# full_board.net
KiCad netlist of a schematic drawn in EAGLE
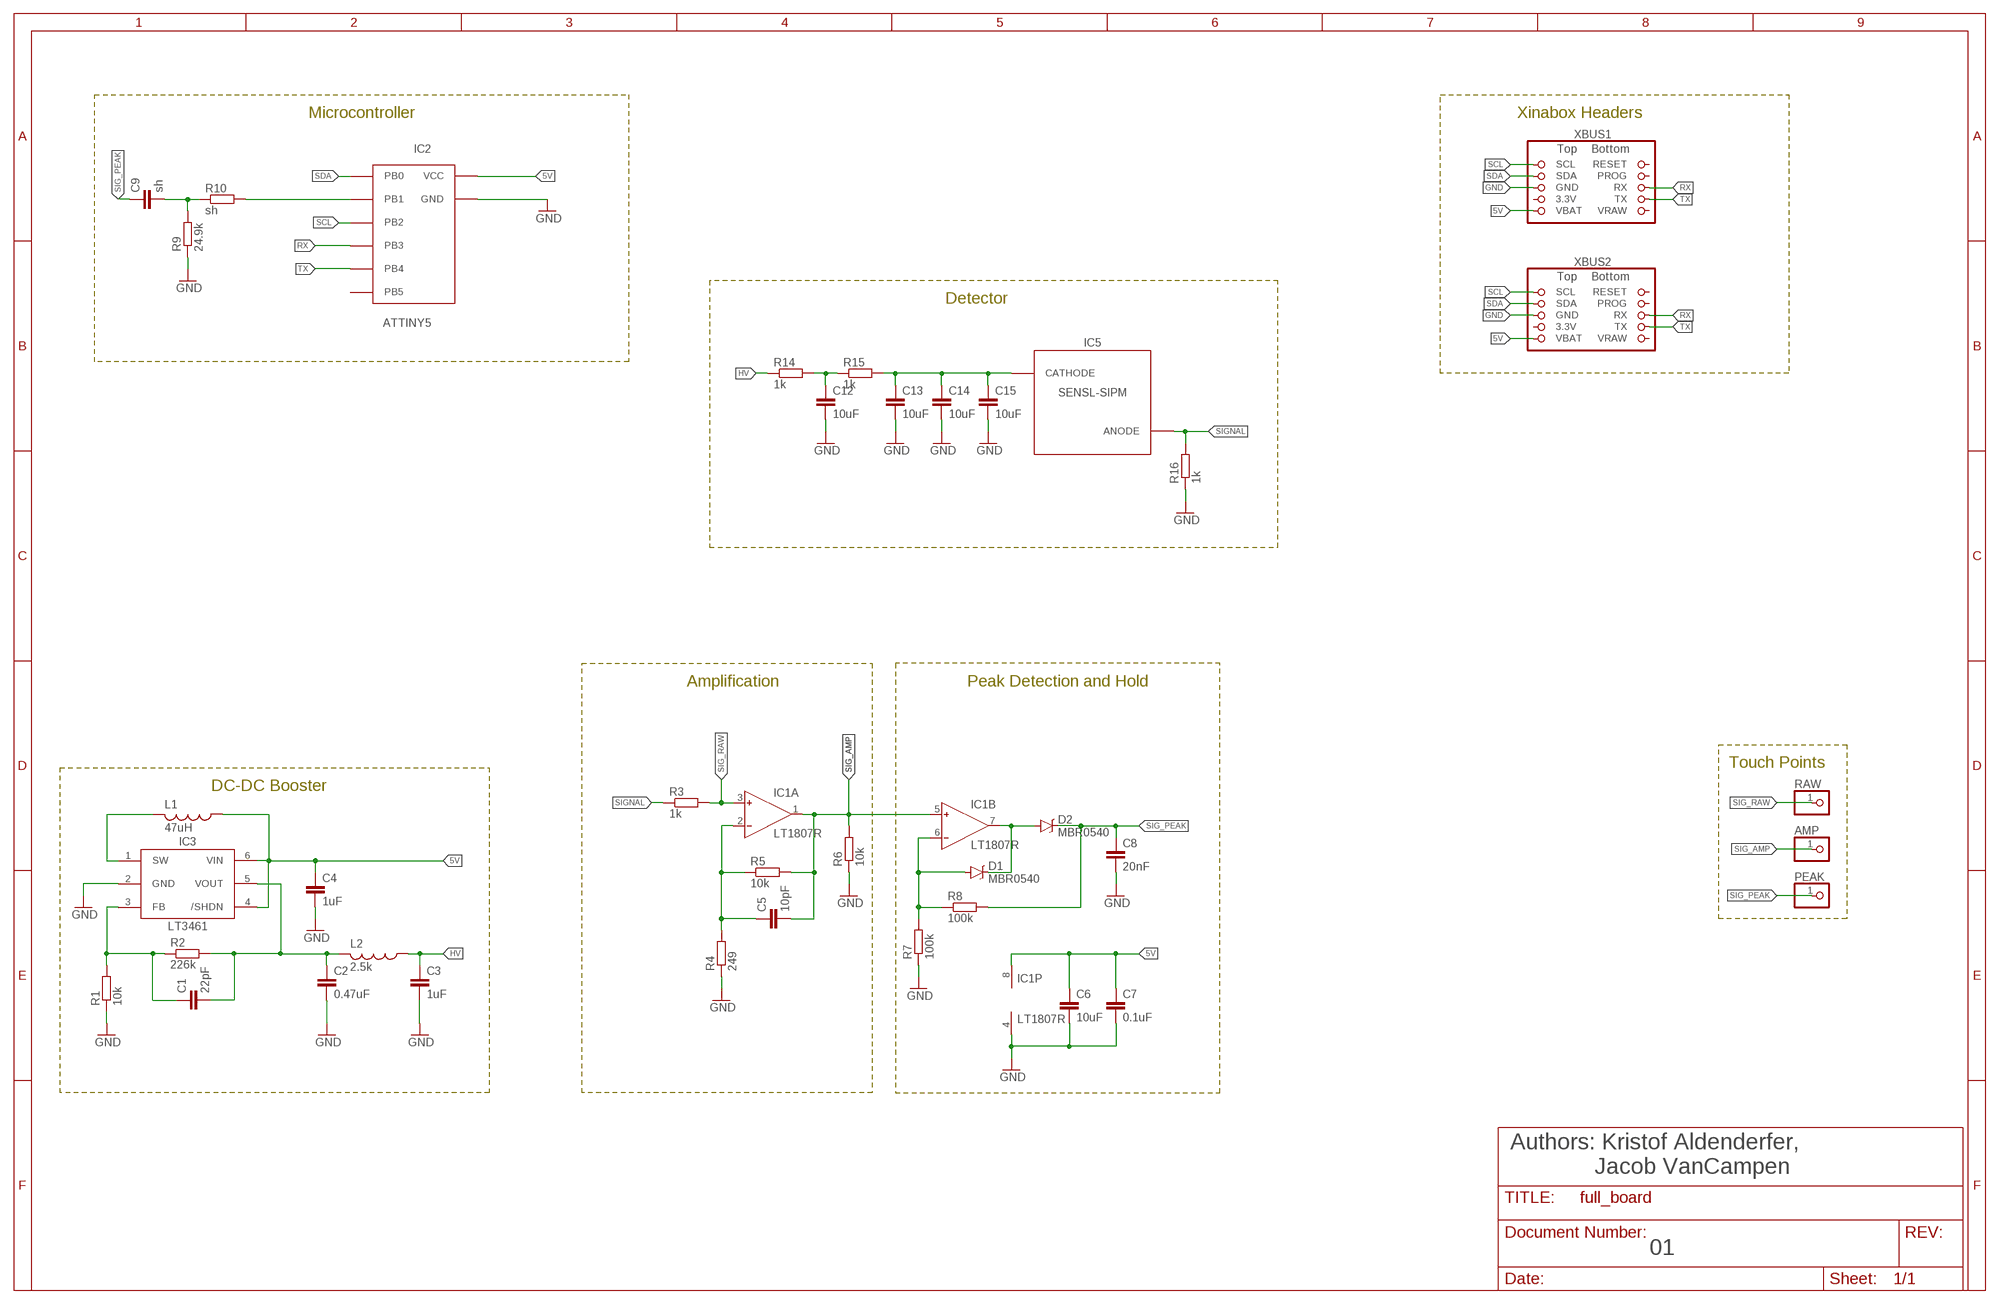
[diagram p0: schematic, sheet 1]

(export (version "E")
  (design (tool "Eeschema 10.0.6"))
  (components
    (comp (ref "AMP")
      (value "PINHD-1X1")
      (footprint "eagle-import:1X01")
      (libsource (lib "eagle-import") (part "PINHD-1X1"))
    )
    (comp (ref "C1")
      (value "22pF")
      (footprint "eagle-import:C0805K")
      (libsource (lib "eagle-import") (part "C-EUC0805K"))
    )
    (comp (ref "C2")
      (value "0.47uF")
      (footprint "eagle-import:C0805K")
      (libsource (lib "eagle-import") (part "C-EUC0805K"))
    )
    (comp (ref "C3")
      (value "1uF")
      (footprint "eagle-import:C0805K")
      (libsource (lib "eagle-import") (part "C-EUC0805K"))
    )
    (comp (ref "C4")
      (value "1uF")
      (footprint "eagle-import:C0805K")
      (libsource (lib "eagle-import") (part "C-EUC0805K"))
    )
    (comp (ref "C5")
      (value "10pF")
      (footprint "eagle-import:C0805K")
      (libsource (lib "eagle-import") (part "C-EUC0805K"))
    )
    (comp (ref "C6")
      (value "10uF")
      (footprint "eagle-import:C0805K")
      (libsource (lib "eagle-import") (part "C-EUC0805K"))
    )
    (comp (ref "C7")
      (value "0.1uF")
      (footprint "eagle-import:C0805K")
      (libsource (lib "eagle-import") (part "C-EUC0805K"))
    )
    (comp (ref "C8")
      (value "20nF")
      (footprint "eagle-import:C0805K")
      (libsource (lib "eagle-import") (part "C-EUC0805K"))
    )
    (comp (ref "C9")
      (value "sh")
      (footprint "eagle-import:C0805K")
      (libsource (lib "eagle-import") (part "C-EUC0805K"))
    )
    (comp (ref "C12")
      (value "10uF")
      (footprint "eagle-import:C0805K")
      (libsource (lib "eagle-import") (part "C-EUC0805K"))
    )
    (comp (ref "C13")
      (value "10uF")
      (footprint "eagle-import:C0805K")
      (libsource (lib "eagle-import") (part "C-EUC0805K"))
    )
    (comp (ref "C14")
      (value "10uF")
      (footprint "eagle-import:C0805K")
      (libsource (lib "eagle-import") (part "C-EUC0805K"))
    )
    (comp (ref "C15")
      (value "10uF")
      (footprint "eagle-import:C0805K")
      (libsource (lib "eagle-import") (part "C-EUC0805K"))
    )
    (comp (ref "D1")
      (value "MBR0540")
      (footprint "eagle-import:SMA-DIODE")
      (libsource (lib "eagle-import") (part "DIODE-SCHOTTKY-B340A"))
    )
    (comp (ref "D2")
      (value "MBR0540")
      (footprint "eagle-import:SMA-DIODE")
      (libsource (lib "eagle-import") (part "DIODE-SCHOTTKY-B340A"))
    )
    (comp (ref "IC1")
      (value "LT1807R")
      (footprint "eagle-import:SO8")
      (fields (field (name "MF") "ALTERA CORPORATION") (field (name "MPN") "AD746JRZ"))
      (libsource (lib "eagle-import") (part "LT1807R"))
    )
    (comp (ref "IC2")
      (value "ATTINY5")
      (footprint "eagle-import:PDIP8")
      (libsource (lib "eagle-import") (part "ATTINY5"))
    )
    (comp (ref "IC3")
      (value "LT3461")
      (footprint "eagle-import:SOT23-6")
      (libsource (lib "eagle-import") (part "LT3461"))
    )
    (comp (ref "IC5")
      (value "SENSL-SIPM")
      (footprint "eagle-import:MICROFC-60035")
      (libsource (lib "eagle-import") (part "SENSL-SIPM"))
    )
    (comp (ref "L1")
      (value "47uH")
      (footprint "eagle-import:L3225M")
      (libsource (lib "eagle-import") (part "rcl_334_L-USL3225M"))
    )
    (comp (ref "L2")
      (value "2.5k")
      (footprint "eagle-import:L2012C")
      (libsource (lib "eagle-import") (part "L-USL2012C"))
    )
    (comp (ref "PEAK")
      (value "PINHD-1X1")
      (footprint "eagle-import:1X01")
      (libsource (lib "eagle-import") (part "PINHD-1X1"))
    )
    (comp (ref "R1")
      (value "10k")
      (footprint "eagle-import:M0805")
      (libsource (lib "eagle-import") (part "R-EU_M0805"))
    )
    (comp (ref "R2")
      (value "226k")
      (footprint "eagle-import:M0805")
      (libsource (lib "eagle-import") (part "R-EU_M0805"))
    )
    (comp (ref "R3")
      (value "1k")
      (footprint "eagle-import:M0805")
      (libsource (lib "eagle-import") (part "R-EU_M0805"))
    )
    (comp (ref "R4")
      (value "249")
      (footprint "eagle-import:M0805")
      (libsource (lib "eagle-import") (part "R-EU_M0805"))
    )
    (comp (ref "R5")
      (value "10k")
      (footprint "eagle-import:M0805")
      (libsource (lib "eagle-import") (part "R-EU_M0805"))
    )
    (comp (ref "R6")
      (value "10k")
      (footprint "eagle-import:M0805")
      (libsource (lib "eagle-import") (part "R-EU_M0805"))
    )
    (comp (ref "R7")
      (value "100k")
      (footprint "eagle-import:M0805")
      (libsource (lib "eagle-import") (part "R-EU_M0805"))
    )
    (comp (ref "R8")
      (value "100k")
      (footprint "eagle-import:M0805")
      (libsource (lib "eagle-import") (part "R-EU_M0805"))
    )
    (comp (ref "R9")
      (value "24.9k")
      (footprint "eagle-import:M0805")
      (libsource (lib "eagle-import") (part "R-EU_M0805"))
    )
    (comp (ref "R10")
      (value "sh")
      (footprint "eagle-import:M0805")
      (libsource (lib "eagle-import") (part "R-EU_M0805"))
    )
    (comp (ref "R14")
      (value "1k")
      (footprint "eagle-import:M0805")
      (libsource (lib "eagle-import") (part "R-EU_M0805"))
    )
    (comp (ref "R15")
      (value "1k")
      (footprint "eagle-import:M0805")
      (libsource (lib "eagle-import") (part "R-EU_M0805"))
    )
    (comp (ref "R16")
      (value "1k")
      (footprint "eagle-import:M0805")
      (libsource (lib "eagle-import") (part "R-EU_M0805"))
    )
    (comp (ref "RAW")
      (value "PINHD-1X1")
      (footprint "eagle-import:1X01")
      (libsource (lib "eagle-import") (part "PINHD-1X1"))
    )
    (comp (ref "XBUS1")
      (value "XINABOX-XBUS")
      (footprint "eagle-import:XBUS_2X05_PAD")
      (libsource (lib "eagle-import") (part "XINABOX-XBUS"))
    )
    (comp (ref "XBUS2")
      (value "XINABOX-XBUS")
      (footprint "eagle-import:XBUS_2X05_PAD")
      (libsource (lib "eagle-import") (part "XINABOX-XBUS"))
    )
  )
  (nets
    (net (code "1") (name "5V") (class "Default")
      (node (ref "C4") (pin "1") (pinfunction "1_1") (pintype "passive"))
      (node (ref "C6") (pin "1") (pinfunction "1_1") (pintype "passive"))
      (node (ref "C7") (pin "1") (pinfunction "1_1") (pintype "passive"))
      (node (ref "IC1") (pin "8") (pinfunction "V+_8") (pintype "power_in"))
      (node (ref "IC2") (pin "P8") (pinfunction "VCC_P8") (pintype "bidirectional"))
      (node (ref "IC3") (pin "4") (pinfunction "/SHDN_4") (pintype "input"))
      (node (ref "IC3") (pin "6") (pinfunction "VIN_6") (pintype "input"))
      (node (ref "L1") (pin "1") (pinfunction "1_1") (pintype "passive"))
      (node (ref "XBUS1") (pin "5") (pinfunction "VBAT_5") (pintype "passive"))
      (node (ref "XBUS2") (pin "5") (pinfunction "VBAT_5") (pintype "passive"))
    )
    (net (code "2") (name "GND") (class "Default")
      (node (ref "C12") (pin "2") (pinfunction "2_2") (pintype "passive"))
      (node (ref "C13") (pin "2") (pinfunction "2_2") (pintype "passive"))
      (node (ref "C14") (pin "2") (pinfunction "2_2") (pintype "passive"))
      (node (ref "C15") (pin "2") (pinfunction "2_2") (pintype "passive"))
      (node (ref "C2") (pin "2") (pinfunction "2_2") (pintype "passive"))
      (node (ref "C3") (pin "2") (pinfunction "2_2") (pintype "passive"))
      (node (ref "C4") (pin "2") (pinfunction "2_2") (pintype "passive"))
      (node (ref "C6") (pin "2") (pinfunction "2_2") (pintype "passive"))
      (node (ref "C7") (pin "2") (pinfunction "2_2") (pintype "passive"))
      (node (ref "C8") (pin "2") (pinfunction "2_2") (pintype "passive"))
      (node (ref "IC1") (pin "4") (pinfunction "V-_4") (pintype "power_in"))
      (node (ref "IC2") (pin "P4") (pinfunction "GND_P4") (pintype "bidirectional"))
      (node (ref "IC3") (pin "2") (pinfunction "GND_2") (pintype "power_in"))
      (node (ref "R1") (pin "1") (pinfunction "1_1") (pintype "passive"))
      (node (ref "R16") (pin "1") (pinfunction "1_1") (pintype "passive"))
      (node (ref "R4") (pin "1") (pinfunction "1_1") (pintype "passive"))
      (node (ref "R6") (pin "1") (pinfunction "1_1") (pintype "passive"))
      (node (ref "R7") (pin "1") (pinfunction "1_1") (pintype "passive"))
      (node (ref "R9") (pin "1") (pinfunction "1_1") (pintype "passive"))
      (node (ref "XBUS1") (pin "3") (pinfunction "GND_3") (pintype "passive"))
      (node (ref "XBUS2") (pin "3") (pinfunction "GND_3") (pintype "passive"))
    )
    (net (code "3") (name "HV") (class "Default")
      (node (ref "C3") (pin "1") (pinfunction "1_1") (pintype "passive"))
      (node (ref "L2") (pin "1") (pinfunction "1_1") (pintype "passive"))
      (node (ref "R14") (pin "1") (pinfunction "1_1") (pintype "passive"))
    )
    (net (code "4") (name "Net-(C9-Pad2)") (class "Default")
      (node (ref "C9") (pin "2") (pinfunction "2_2") (pintype "passive"))
      (node (ref "R10") (pin "1") (pinfunction "1_1") (pintype "passive"))
      (node (ref "R9") (pin "2") (pinfunction "2_2") (pintype "passive"))
    )
    (net (code "5") (name "Net-(C12-Pad1)") (class "Default")
      (node (ref "C12") (pin "1") (pinfunction "1_1") (pintype "passive"))
      (node (ref "R14") (pin "2") (pinfunction "2_2") (pintype "passive"))
      (node (ref "R15") (pin "1") (pinfunction "1_1") (pintype "passive"))
    )
    (net (code "6") (name "Net-(C13-Pad1)") (class "Default")
      (node (ref "C13") (pin "1") (pinfunction "1_1") (pintype "passive"))
      (node (ref "C14") (pin "1") (pinfunction "1_1") (pintype "passive"))
      (node (ref "C15") (pin "1") (pinfunction "1_1") (pintype "passive"))
      (node (ref "IC5") (pin "CATHODE") (pinfunction "CATHODE_CATHODE") (pintype "bidirectional"))
      (node (ref "R15") (pin "2") (pinfunction "2_2") (pintype "passive"))
    )
    (net (code "7") (name "Net-(IC1A-IN-)") (class "Default")
      (node (ref "C5") (pin "1") (pinfunction "1_1") (pintype "passive"))
      (node (ref "IC1") (pin "2") (pinfunction "IN-_2") (pintype "input"))
      (node (ref "R4") (pin "2") (pinfunction "2_2") (pintype "passive"))
      (node (ref "R5") (pin "1") (pinfunction "1_1") (pintype "passive"))
    )
    (net (code "8") (name "Net-(IC1B-IN-)") (class "Default")
      (node (ref "D1") (pin "A") (pinfunction "A_A") (pintype "passive"))
      (node (ref "IC1") (pin "6") (pinfunction "IN-_6") (pintype "input"))
      (node (ref "R7") (pin "2") (pinfunction "2_2") (pintype "passive"))
      (node (ref "R8") (pin "1") (pinfunction "1_1") (pintype "passive"))
    )
    (net (code "9") (name "Net-(IC1B-OUT)") (class "Default")
      (node (ref "D1") (pin "C") (pinfunction "C_C") (pintype "passive"))
      (node (ref "D2") (pin "A") (pinfunction "A_A") (pintype "passive"))
      (node (ref "IC1") (pin "7") (pinfunction "OUT_7") (pintype "output"))
    )
    (net (code "10") (name "Net-(IC2-PB1)") (class "Default")
      (node (ref "IC2") (pin "P6") (pinfunction "PB1_P6") (pintype "bidirectional"))
      (node (ref "R10") (pin "2") (pinfunction "2_2") (pintype "passive"))
    )
    (net (code "11") (name "Net-(IC3-FB)") (class "Default")
      (node (ref "C1") (pin "1") (pinfunction "1_1") (pintype "passive"))
      (node (ref "IC3") (pin "3") (pinfunction "FB_3") (pintype "input"))
      (node (ref "R1") (pin "2") (pinfunction "2_2") (pintype "passive"))
      (node (ref "R2") (pin "1") (pinfunction "1_1") (pintype "passive"))
    )
    (net (code "12") (name "Net-(IC3-SW)") (class "Default")
      (node (ref "IC3") (pin "1") (pinfunction "SW_1") (pintype "output"))
      (node (ref "L1") (pin "2") (pinfunction "2_2") (pintype "passive"))
    )
    (net (code "13") (name "Net-(IC3-VOUT)") (class "Default")
      (node (ref "C1") (pin "2") (pinfunction "2_2") (pintype "passive"))
      (node (ref "C2") (pin "1") (pinfunction "1_1") (pintype "passive"))
      (node (ref "IC3") (pin "5") (pinfunction "VOUT_5") (pintype "output"))
      (node (ref "L2") (pin "2") (pinfunction "2_2") (pintype "passive"))
      (node (ref "R2") (pin "2") (pinfunction "2_2") (pintype "passive"))
    )
    (net (code "14") (name "RX") (class "Default")
      (node (ref "IC2") (pin "P2") (pinfunction "PB3_P2") (pintype "bidirectional"))
      (node (ref "XBUS1") (pin "8") (pinfunction "RX_8") (pintype "passive"))
      (node (ref "XBUS2") (pin "8") (pinfunction "RX_8") (pintype "passive"))
    )
    (net (code "15") (name "SCL") (class "Default")
      (node (ref "IC2") (pin "P7") (pinfunction "PB2_P7") (pintype "bidirectional"))
      (node (ref "XBUS1") (pin "1") (pinfunction "SCL_1") (pintype "passive"))
      (node (ref "XBUS2") (pin "1") (pinfunction "SCL_1") (pintype "passive"))
    )
    (net (code "16") (name "SDA") (class "Default")
      (node (ref "IC2") (pin "P5") (pinfunction "PB0_P5") (pintype "bidirectional"))
      (node (ref "XBUS1") (pin "2") (pinfunction "SDA_2") (pintype "passive"))
      (node (ref "XBUS2") (pin "2") (pinfunction "SDA_2") (pintype "passive"))
    )
    (net (code "17") (name "SIGNAL") (class "Default")
      (node (ref "IC5") (pin "ANODE") (pinfunction "ANODE_ANODE") (pintype "bidirectional"))
      (node (ref "R16") (pin "2") (pinfunction "2_2") (pintype "passive"))
      (node (ref "R3") (pin "1") (pinfunction "1_1") (pintype "passive"))
    )
    (net (code "18") (name "SIG_AMP") (class "Default")
      (node (ref "AMP") (pin "1") (pinfunction "1_1") (pintype "passive"))
      (node (ref "C5") (pin "2") (pinfunction "2_2") (pintype "passive"))
      (node (ref "IC1") (pin "1") (pinfunction "OUT_1") (pintype "output"))
      (node (ref "IC1") (pin "5") (pinfunction "IN+_5") (pintype "input"))
      (node (ref "R5") (pin "2") (pinfunction "2_2") (pintype "passive"))
      (node (ref "R6") (pin "2") (pinfunction "2_2") (pintype "passive"))
    )
    (net (code "19") (name "SIG_PEAK") (class "Default")
      (node (ref "C8") (pin "1") (pinfunction "1_1") (pintype "passive"))
      (node (ref "C9") (pin "1") (pinfunction "1_1") (pintype "passive"))
      (node (ref "D2") (pin "C") (pinfunction "C_C") (pintype "passive"))
      (node (ref "PEAK") (pin "1") (pinfunction "1_1") (pintype "passive"))
      (node (ref "R8") (pin "2") (pinfunction "2_2") (pintype "passive"))
    )
    (net (code "20") (name "SIG_RAW") (class "Default")
      (node (ref "IC1") (pin "3") (pinfunction "IN+_3") (pintype "input"))
      (node (ref "R3") (pin "2") (pinfunction "2_2") (pintype "passive"))
      (node (ref "RAW") (pin "1") (pinfunction "1_1") (pintype "passive"))
    )
    (net (code "21") (name "TX") (class "Default")
      (node (ref "IC2") (pin "P3") (pinfunction "PB4_P3") (pintype "bidirectional"))
      (node (ref "XBUS1") (pin "9") (pinfunction "TX_9") (pintype "passive"))
      (node (ref "XBUS2") (pin "9") (pinfunction "TX_9") (pintype "passive"))
    )
    (net (code "22") (name "unconnected-(IC2-PB5-PadP1)") (class "Default")
      (node (ref "IC2") (pin "P1") (pinfunction "PB5_P1") (pintype "bidirectional"))
    )
    (net (code "23") (name "unconnected-(XBUS1-3.3V-Pad4)") (class "Default")
      (node (ref "XBUS1") (pin "4") (pinfunction "3.3V_4") (pintype "passive"))
    )
    (net (code "24") (name "unconnected-(XBUS1-PROG-Pad7)") (class "Default")
      (node (ref "XBUS1") (pin "7") (pinfunction "PROG_7") (pintype "passive"))
    )
    (net (code "25") (name "unconnected-(XBUS1-RESET-Pad6)") (class "Default")
      (node (ref "XBUS1") (pin "6") (pinfunction "RESET_6") (pintype "passive"))
    )
    (net (code "26") (name "unconnected-(XBUS1-VRAW-Pad10)") (class "Default")
      (node (ref "XBUS1") (pin "10") (pinfunction "VRAW_10") (pintype "passive"))
    )
    (net (code "27") (name "unconnected-(XBUS2-3.3V-Pad4)") (class "Default")
      (node (ref "XBUS2") (pin "4") (pinfunction "3.3V_4") (pintype "passive"))
    )
    (net (code "28") (name "unconnected-(XBUS2-PROG-Pad7)") (class "Default")
      (node (ref "XBUS2") (pin "7") (pinfunction "PROG_7") (pintype "passive"))
    )
    (net (code "29") (name "unconnected-(XBUS2-RESET-Pad6)") (class "Default")
      (node (ref "XBUS2") (pin "6") (pinfunction "RESET_6") (pintype "passive"))
    )
    (net (code "30") (name "unconnected-(XBUS2-VRAW-Pad10)") (class "Default")
      (node (ref "XBUS2") (pin "10") (pinfunction "VRAW_10") (pintype "passive"))
    )
  )
)
